# Sensors.net
KiCad netlist of a schematic drawn in Altium Designer
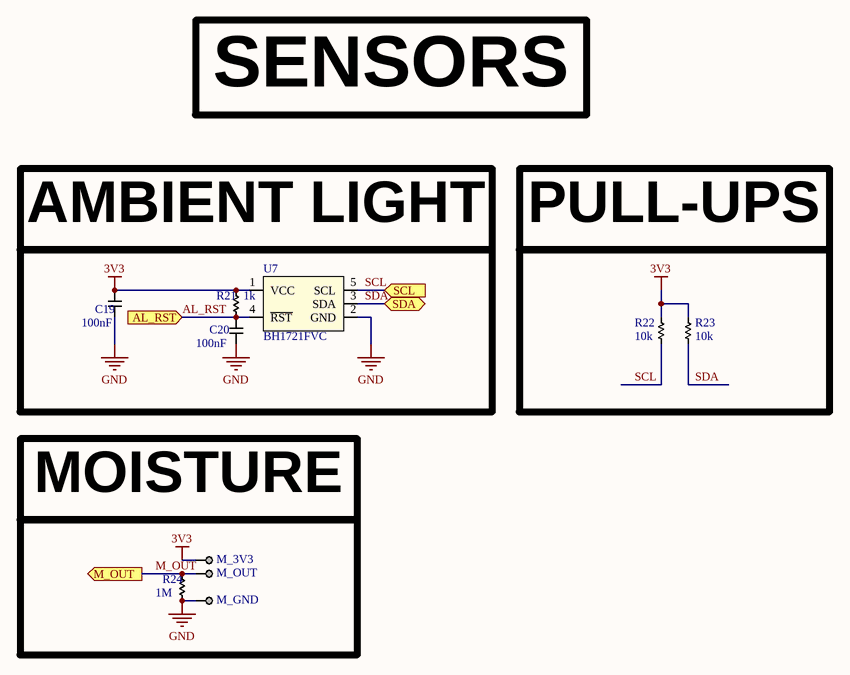
[diagram p0: Sensors.SchDoc]

(export (version "E")
  (design (tool "Eeschema 10.0.6"))
  (components
    (comp (ref "C19")
      (value "100nF")
      (footprint "CAP_0402_HIGH")
      (description "0402 Capacitor")
      (libsource (lib "smLib") (part "Capacitor_0402"))
    )
    (comp (ref "C20")
      (value "100nF")
      (footprint "CAP_0402_HIGH")
      (description "0402 Capacitor")
      (libsource (lib "smLib") (part "Capacitor_0402"))
    )
    (comp (ref "M_3V3")
      (value "0.1\" Header")
      (footprint "0.1\" Header")
      (libsource (lib "smLib") (part "0.1{dblquote} Header"))
    )
    (comp (ref "M_GND")
      (value "0.1\" Header")
      (footprint "0.1\" Header")
      (libsource (lib "smLib") (part "0.1{dblquote} Header"))
    )
    (comp (ref "M_OUT")
      (value "0.1\" Header")
      (footprint "0.1\" Header")
      (libsource (lib "smLib") (part "0.1{dblquote} Header"))
    )
    (comp (ref "R21")
      (value "1k")
      (footprint "RES_0402_HIGH")
      (description "0402 Resistor")
      (libsource (lib "smLib") (part "Resistor_0402"))
    )
    (comp (ref "R22")
      (value "10k")
      (footprint "RES_0402_HIGH")
      (description "0402 Resistor")
      (libsource (lib "smLib") (part "Resistor_0402"))
    )
    (comp (ref "R23")
      (value "10k")
      (footprint "RES_0402_HIGH")
      (description "0402 Resistor")
      (libsource (lib "smLib") (part "Resistor_0402"))
    )
    (comp (ref "R24")
      (value "1M")
      (footprint "RES_0402_HIGH")
      (description "0402 Resistor")
      (libsource (lib "smLib") (part "Resistor_0402"))
    )
    (comp (ref "U7")
      (value "BH1721FVC")
      (footprint "BH1721FVC")
      (description "BH1721FVC Optical Sensor Ambient 560nm I²C 5-SMD, Flat Leads")
      (libsource (lib "smLib") (part "BH1721FVC"))
    )
  )
  (nets
    (net (code "1") (name "/AL_RST") (class "Default")
      (node (ref "C20") (pin "2") (pinfunction "2_2") (pintype "passive"))
      (node (ref "R21") (pin "1") (pinfunction "1_1") (pintype "passive"))
      (node (ref "U7") (pin "4") (pinfunction "~{RST}_4") (pintype "passive"))
    )
    (net (code "2") (name "/M_OUT") (class "Default")
      (node (ref "M_OUT") (pin "1") (pinfunction "1_1") (pintype "passive"))
      (node (ref "R24") (pin "2") (pinfunction "2_2") (pintype "passive"))
    )
    (net (code "3") (name "/SCL") (class "Default")
      (node (ref "R22") (pin "1") (pinfunction "1_1") (pintype "passive"))
      (node (ref "U7") (pin "5") (pinfunction "SCL_5") (pintype "passive"))
    )
    (net (code "4") (name "/SDA") (class "Default")
      (node (ref "R23") (pin "1") (pinfunction "1_1") (pintype "passive"))
      (node (ref "U7") (pin "3") (pinfunction "SDA_3") (pintype "passive"))
    )
    (net (code "5") (name "3V3") (class "Default")
      (node (ref "C19") (pin "2") (pinfunction "2_2") (pintype "passive"))
      (node (ref "M_3V3") (pin "1") (pinfunction "1_1") (pintype "passive"))
      (node (ref "R21") (pin "2") (pinfunction "2_2") (pintype "passive"))
      (node (ref "R22") (pin "2") (pinfunction "2_2") (pintype "passive"))
      (node (ref "R23") (pin "2") (pinfunction "2_2") (pintype "passive"))
      (node (ref "U7") (pin "1") (pinfunction "VCC_1") (pintype "passive"))
    )
    (net (code "6") (name "GND") (class "Default")
      (node (ref "C19") (pin "1") (pinfunction "1_1") (pintype "passive"))
      (node (ref "C20") (pin "1") (pinfunction "1_1") (pintype "passive"))
      (node (ref "M_GND") (pin "1") (pinfunction "1_1") (pintype "passive"))
      (node (ref "R24") (pin "1") (pinfunction "1_1") (pintype "passive"))
      (node (ref "U7") (pin "2") (pinfunction "GND_2") (pintype "passive"))
    )
  )
)
